# Power.net
KiCad netlist of a schematic drawn in Altium Designer
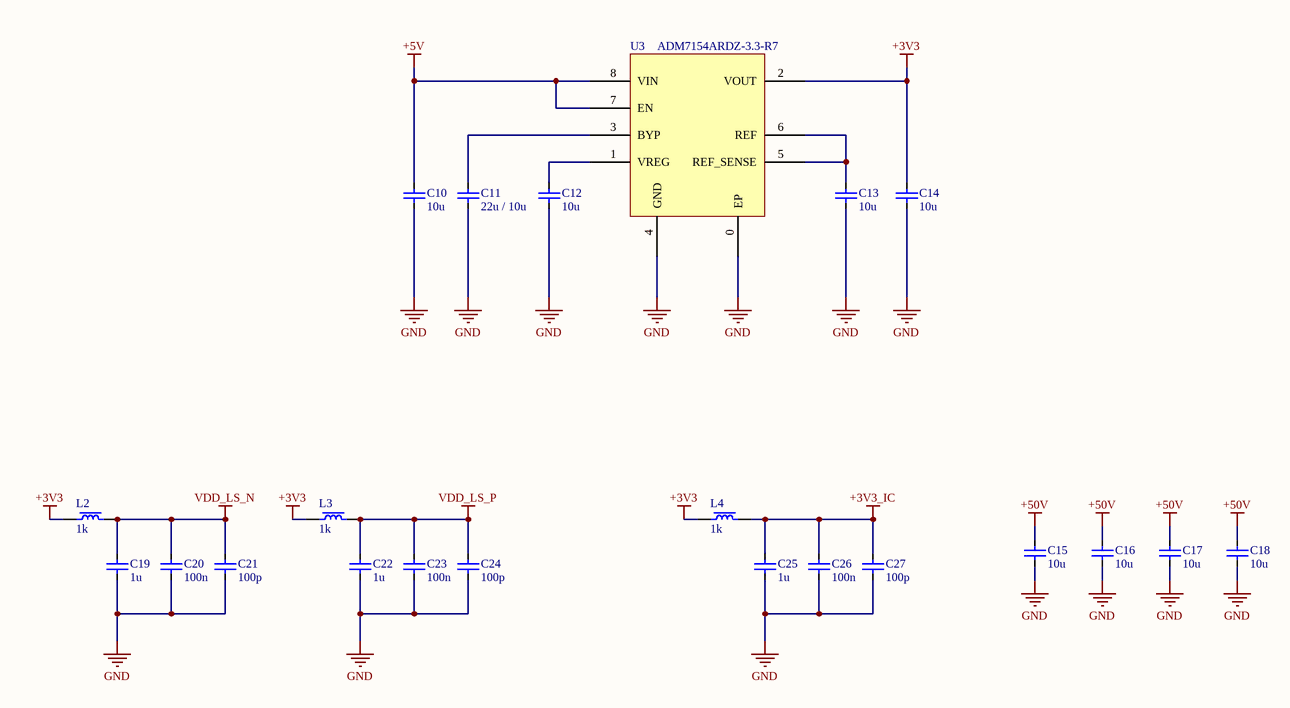
[diagram p0: Power.SchDoc]

(export (version "E")
  (design (tool "Eeschema 10.0.6"))
  (components
    (comp (ref "C10") (value "10u") (footprint "CAP_0603") (libsource (lib "IIS-Lib_TW") (part "Cap")))
    (comp (ref "C11") (value "22u / 10u") (footprint "CAP_0603") (libsource (lib "IIS-Lib_TW") (part "Cap")))
    (comp (ref "C12") (value "10u") (footprint "CAP_0603") (libsource (lib "IIS-Lib_TW") (part "Cap")))
    (comp (ref "C13") (value "10u") (footprint "CAP_0603") (libsource (lib "IIS-Lib_TW") (part "Cap")))
    (comp (ref "C14") (value "10u") (footprint "CAP_0603") (libsource (lib "IIS-Lib_TW") (part "Cap")))
    (comp (ref "C15") (value "10u") (footprint "CAP_0805") (libsource (lib "IIS-Lib_TW") (part "Cap")))
    (comp (ref "C16") (value "10u") (footprint "CAP_0805") (libsource (lib "IIS-Lib_TW") (part "Cap")))
    (comp (ref "C17") (value "10u") (footprint "CAP_0805") (libsource (lib "IIS-Lib_TW") (part "Cap")))
    (comp (ref "C18") (value "10u") (footprint "CAP_0805") (libsource (lib "IIS-Lib_TW") (part "Cap")))
    (comp (ref "C19") (value "1u") (footprint "CAP_0603") (libsource (lib "IIS-Lib_TW") (part "Cap")))
    (comp (ref "C20") (value "100n") (footprint "CAP_0603") (libsource (lib "IIS-Lib_TW") (part "Cap")))
    (comp (ref "C21") (value "100p") (footprint "CAP_0603") (libsource (lib "IIS-Lib_TW") (part "Cap")))
    (comp (ref "C22") (value "1u") (footprint "CAP_0603") (libsource (lib "IIS-Lib_TW") (part "Cap")))
    (comp (ref "C23") (value "100n") (footprint "CAP_0603") (libsource (lib "IIS-Lib_TW") (part "Cap")))
    (comp (ref "C24") (value "100p") (footprint "CAP_0603") (libsource (lib "IIS-Lib_TW") (part "Cap")))
    (comp (ref "C25") (value "1u") (footprint "CAP_0603") (libsource (lib "IIS-Lib_TW") (part "Cap")))
    (comp (ref "C26") (value "100n") (footprint "CAP_0603") (libsource (lib "IIS-Lib_TW") (part "Cap")))
    (comp (ref "C27") (value "100p") (footprint "CAP_0603") (libsource (lib "IIS-Lib_TW") (part "Cap")))
    (comp (ref "L2") (value "1k") (footprint "CAP_0603") (libsource (lib "IIS-Lib_TW") (part "FerriteBead")))
    (comp (ref "L3") (value "1k") (footprint "CAP_0603") (libsource (lib "IIS-Lib_TW") (part "FerriteBead")))
    (comp (ref "L4") (value "1k") (footprint "CAP_0603") (libsource (lib "IIS-Lib_TW") (part "FerriteBead")))
    (comp (ref "U3")
      (value "ADM7154ARDZ-3.3-R7")
      (footprint "SOIC-8_TP")
      (libsource (lib "IIS-Lib_TW") (part "ADM715X"))
    )
  )
  (nets
    (net (code "1") (name "+3V3") (class "Default")
      (node (ref "C14") (pin "1") (pinfunction "1_1") (pintype "passive"))
      (node (ref "L2") (pin "1") (pinfunction "1_1") (pintype "passive"))
      (node (ref "L3") (pin "1") (pinfunction "1_1") (pintype "passive"))
      (node (ref "L4") (pin "1") (pinfunction "1_1") (pintype "passive"))
      (node (ref "U3") (pin "2") (pinfunction "VOUT_2") (pintype "passive"))
    )
    (net (code "2") (name "+3V3_IC") (class "Default")
      (node (ref "C25") (pin "1") (pinfunction "1_1") (pintype "passive"))
      (node (ref "C26") (pin "1") (pinfunction "1_1") (pintype "passive"))
      (node (ref "C27") (pin "1") (pinfunction "1_1") (pintype "passive"))
      (node (ref "L4") (pin "2") (pinfunction "2_2") (pintype "passive"))
    )
    (net (code "3") (name "+5V") (class "Default")
      (node (ref "C10") (pin "1") (pinfunction "1_1") (pintype "passive"))
      (node (ref "U3") (pin "7") (pinfunction "EN_7") (pintype "passive"))
      (node (ref "U3") (pin "8") (pinfunction "VIN_8") (pintype "passive"))
    )
    (net (code "4") (name "+50V") (class "Default")
      (node (ref "C15") (pin "1") (pinfunction "1_1") (pintype "passive"))
      (node (ref "C16") (pin "1") (pinfunction "1_1") (pintype "passive"))
      (node (ref "C17") (pin "1") (pinfunction "1_1") (pintype "passive"))
      (node (ref "C18") (pin "1") (pinfunction "1_1") (pintype "passive"))
    )
    (net (code "5") (name "GND") (class "Default")
      (node (ref "C10") (pin "2") (pinfunction "2_2") (pintype "passive"))
      (node (ref "C11") (pin "2") (pinfunction "2_2") (pintype "passive"))
      (node (ref "C12") (pin "2") (pinfunction "2_2") (pintype "passive"))
      (node (ref "C13") (pin "2") (pinfunction "2_2") (pintype "passive"))
      (node (ref "C14") (pin "2") (pinfunction "2_2") (pintype "passive"))
      (node (ref "C15") (pin "2") (pinfunction "2_2") (pintype "passive"))
      (node (ref "C16") (pin "2") (pinfunction "2_2") (pintype "passive"))
      (node (ref "C17") (pin "2") (pinfunction "2_2") (pintype "passive"))
      (node (ref "C18") (pin "2") (pinfunction "2_2") (pintype "passive"))
      (node (ref "C19") (pin "2") (pinfunction "2_2") (pintype "passive"))
      (node (ref "C20") (pin "2") (pinfunction "2_2") (pintype "passive"))
      (node (ref "C21") (pin "2") (pinfunction "2_2") (pintype "passive"))
      (node (ref "C22") (pin "2") (pinfunction "2_2") (pintype "passive"))
      (node (ref "C23") (pin "2") (pinfunction "2_2") (pintype "passive"))
      (node (ref "C24") (pin "2") (pinfunction "2_2") (pintype "passive"))
      (node (ref "C25") (pin "2") (pinfunction "2_2") (pintype "passive"))
      (node (ref "C26") (pin "2") (pinfunction "2_2") (pintype "passive"))
      (node (ref "C27") (pin "2") (pinfunction "2_2") (pintype "passive"))
      (node (ref "U3") (pin "0") (pinfunction "EP_0") (pintype "passive"))
      (node (ref "U3") (pin "4") (pinfunction "GND_4") (pintype "passive"))
    )
    (net (code "6") (name "Net-(U3-BYP)") (class "Default")
      (node (ref "C11") (pin "1") (pinfunction "1_1") (pintype "passive"))
      (node (ref "U3") (pin "3") (pinfunction "BYP_3") (pintype "passive"))
    )
    (net (code "7") (name "Net-(U3-REF)") (class "Default")
      (node (ref "C13") (pin "1") (pinfunction "1_1") (pintype "passive"))
      (node (ref "U3") (pin "5") (pinfunction "REF_SENSE_5") (pintype "passive"))
      (node (ref "U3") (pin "6") (pinfunction "REF_6") (pintype "passive"))
    )
    (net (code "8") (name "Net-(U3-VREG)") (class "Default")
      (node (ref "C12") (pin "1") (pinfunction "1_1") (pintype "passive"))
      (node (ref "U3") (pin "1") (pinfunction "VREG_1") (pintype "passive"))
    )
    (net (code "9") (name "VDD_LS_N") (class "Default")
      (node (ref "C19") (pin "1") (pinfunction "1_1") (pintype "passive"))
      (node (ref "C20") (pin "1") (pinfunction "1_1") (pintype "passive"))
      (node (ref "C21") (pin "1") (pinfunction "1_1") (pintype "passive"))
      (node (ref "L2") (pin "2") (pinfunction "2_2") (pintype "passive"))
    )
    (net (code "10") (name "VDD_LS_P") (class "Default")
      (node (ref "C22") (pin "1") (pinfunction "1_1") (pintype "passive"))
      (node (ref "C23") (pin "1") (pinfunction "1_1") (pintype "passive"))
      (node (ref "C24") (pin "1") (pinfunction "1_1") (pintype "passive"))
      (node (ref "L3") (pin "2") (pinfunction "2_2") (pintype "passive"))
    )
  )
)
